# SCH_Force_Plate_Signal_Conditioning_Unit.net
KiCad netlist of a schematic drawn in EasyEDA
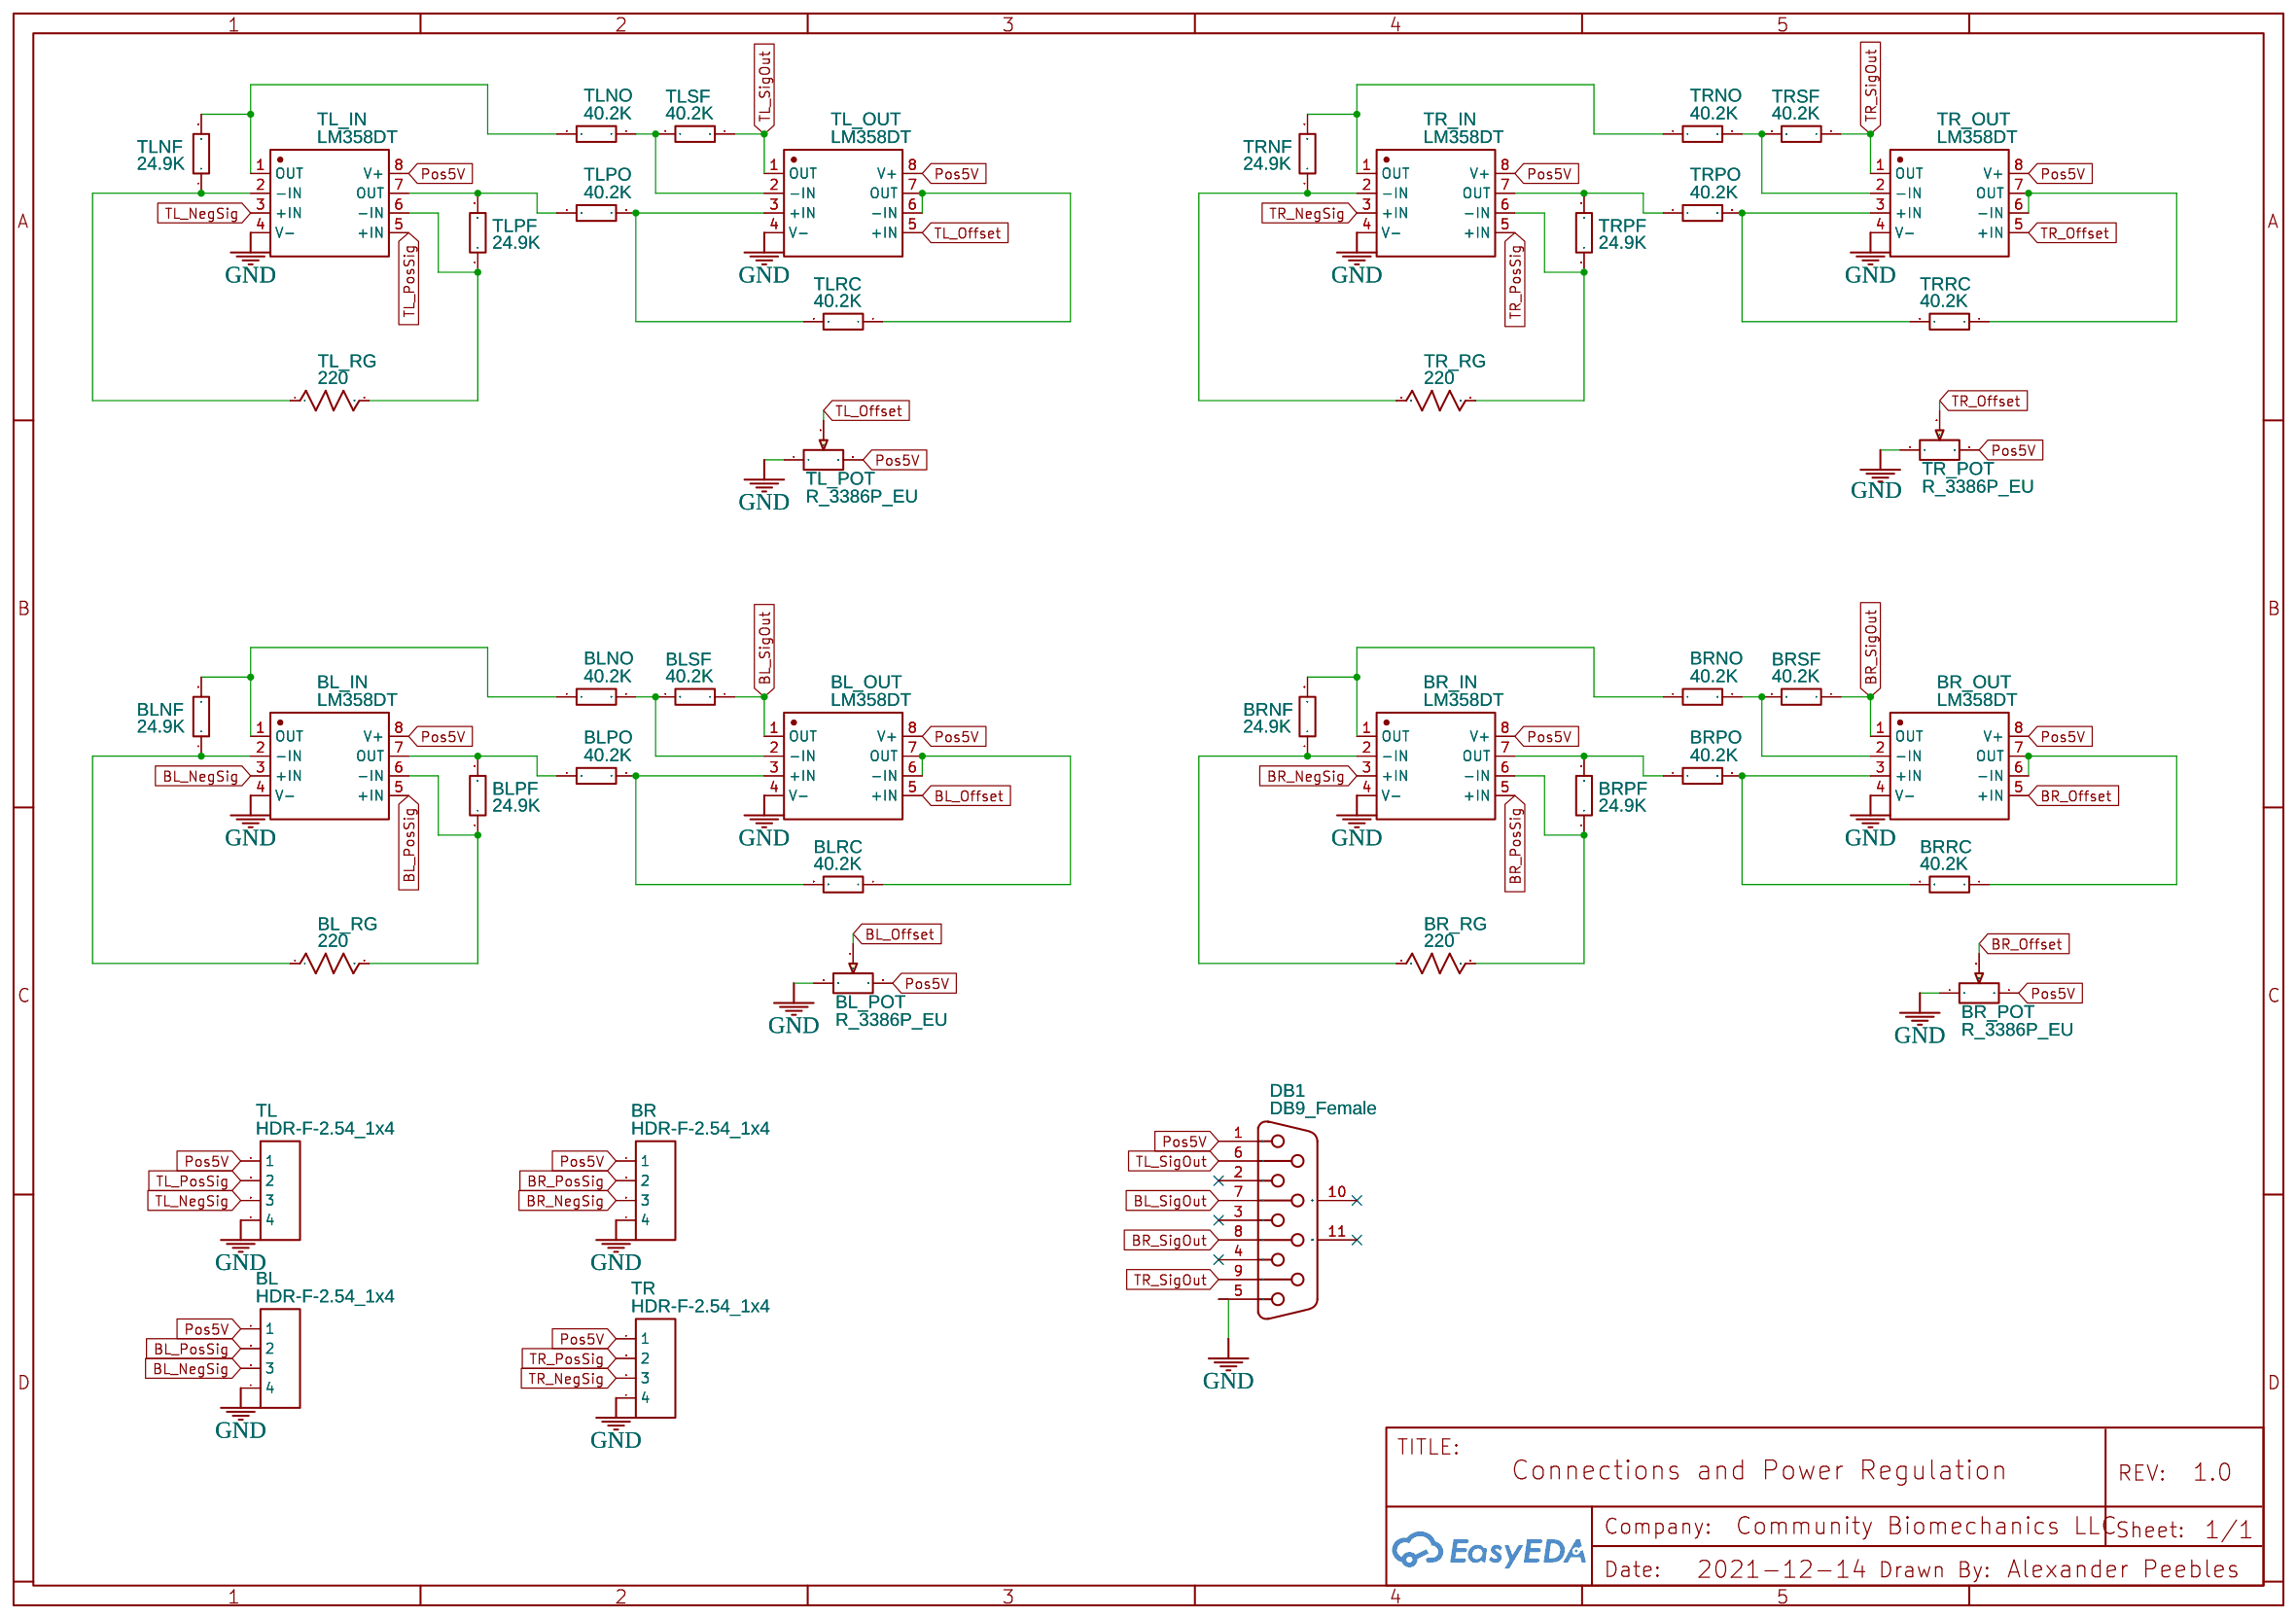
[diagram p0: schematic sheet]

(export (version "E")
  (design (tool "Eeschema 10.0.6"))
  (components
    (comp (ref "BL")
      (value "HDR-F-2.54_1x4")
      (fields (field (name "BOM_Supplier Part") "C225501"))
      (libsource (lib "") (part "HDR-F-2.54_1x4_1"))
    )
    (comp (ref "BLNF")
      (value "24.9K")
      (fields
        (field (name "BOM_Manufacturer Part") "0603WAF2492T5E")
        (field (name "BOM_Supplier Part") "C25962")
      )
      (libsource (lib "") (part "0603WAF2492T5E_7"))
    )
    (comp (ref "BLNO")
      (value "40.2K")
      (fields
        (field (name "BOM_Manufacturer Part") "0603WAF4022T5E")
        (field (name "BOM_Supplier Part") "C12447")
      )
      (libsource (lib "") (part "0603WAF4022T5E_8"))
    )
    (comp (ref "BLPF")
      (value "24.9K")
      (fields
        (field (name "BOM_Manufacturer Part") "0603WAF2492T5E")
        (field (name "BOM_Supplier Part") "C25962")
      )
      (libsource (lib "") (part "0603WAF2492T5E_2"))
    )
    (comp (ref "BLPO")
      (value "40.2K")
      (fields
        (field (name "BOM_Manufacturer Part") "0603WAF4022T5E")
        (field (name "BOM_Supplier Part") "C12447")
      )
      (libsource (lib "") (part "0603WAF4022T5E_11"))
    )
    (comp (ref "BLRC")
      (value "40.2K")
      (fields
        (field (name "BOM_Manufacturer Part") "0603WAF4022T5E")
        (field (name "BOM_Supplier Part") "C12447")
      )
      (libsource (lib "") (part "0603WAF4022T5E_1"))
    )
    (comp (ref "BLSF")
      (value "40.2K")
      (fields
        (field (name "BOM_Manufacturer Part") "0603WAF4022T5E")
        (field (name "BOM_Supplier Part") "C12447")
      )
      (libsource (lib "") (part "0603WAF4022T5E_15"))
    )
    (comp (ref "BL_IN")
      (value "LM358DT")
      (fields (field (name "BOM_Supplier Part") "C9418"))
      (libsource (lib "") (part "LM358DT_1"))
    )
    (comp (ref "BL_OUT")
      (value "LM358DT")
      (fields (field (name "BOM_Supplier Part") "C9418"))
      (libsource (lib "") (part "LM358DT_5"))
    )
    (comp (ref "BL_POT") (value "R_3386P_EU") (libsource (lib "") (part "R_3386P_EU_2")))
    (comp (ref "BL_RG") (value "220") (libsource (lib "") (part "R_AXIAL-0.4_US")))
    (comp (ref "BR")
      (value "HDR-F-2.54_1x4")
      (fields (field (name "BOM_Supplier Part") "C225501"))
      (libsource (lib "") (part "HDR-F-2.54_1x4"))
    )
    (comp (ref "BRNF")
      (value "24.9K")
      (fields
        (field (name "BOM_Manufacturer Part") "0603WAF2492T5E")
        (field (name "BOM_Supplier Part") "C25962")
      )
      (libsource (lib "") (part "0603WAF2492T5E_3"))
    )
    (comp (ref "BRNO")
      (value "40.2K")
      (fields
        (field (name "BOM_Manufacturer Part") "0603WAF4022T5E")
        (field (name "BOM_Supplier Part") "C12447")
      )
      (libsource (lib "") (part "0603WAF4022T5E_3"))
    )
    (comp (ref "BRPF")
      (value "24.9K")
      (fields
        (field (name "BOM_Manufacturer Part") "0603WAF2492T5E")
        (field (name "BOM_Supplier Part") "C25962")
      )
      (libsource (lib "") (part "0603WAF2492T5E_6"))
    )
    (comp (ref "BRPO")
      (value "40.2K")
      (fields
        (field (name "BOM_Manufacturer Part") "0603WAF4022T5E")
        (field (name "BOM_Supplier Part") "C12447")
      )
      (libsource (lib "") (part "0603WAF4022T5E_14"))
    )
    (comp (ref "BRRC")
      (value "40.2K")
      (fields
        (field (name "BOM_Manufacturer Part") "0603WAF4022T5E")
        (field (name "BOM_Supplier Part") "C12447")
      )
      (libsource (lib "") (part "0603WAF4022T5E_13"))
    )
    (comp (ref "BRSF")
      (value "40.2K")
      (fields
        (field (name "BOM_Manufacturer Part") "0603WAF4022T5E")
        (field (name "BOM_Supplier Part") "C12447")
      )
      (libsource (lib "") (part "0603WAF4022T5E_10"))
    )
    (comp (ref "BR_IN")
      (value "LM358DT")
      (fields (field (name "BOM_Supplier Part") "C9418"))
      (libsource (lib "") (part "LM358DT_2"))
    )
    (comp (ref "BR_OUT")
      (value "LM358DT")
      (fields (field (name "BOM_Supplier Part") "C9418"))
      (libsource (lib "") (part "LM358DT_3"))
    )
    (comp (ref "BR_POT") (value "R_3386P_EU") (libsource (lib "") (part "R_3386P_EU")))
    (comp (ref "BR_RG") (value "220") (libsource (lib "") (part "R_AXIAL-0.4_US_2")))
    (comp (ref "DB1")
      (value "DB9_Female")
      (fields (field (name "BOM_Supplier Part") "C141882"))
      (libsource (lib "") (part "DB9_Female"))
    )
    (comp (ref "TL")
      (value "HDR-F-2.54_1x4")
      (fields (field (name "BOM_Supplier Part") "C225501"))
      (libsource (lib "") (part "HDR-F-2.54_1x4_3"))
    )
    (comp (ref "TLNF")
      (value "24.9K")
      (fields
        (field (name "BOM_Manufacturer Part") "0603WAF2492T5E")
        (field (name "BOM_Supplier Part") "C25962")
      )
      (libsource (lib "") (part "0603WAF2492T5E_5"))
    )
    (comp (ref "TLNO")
      (value "40.2K")
      (fields
        (field (name "BOM_Manufacturer Part") "0603WAF4022T5E")
        (field (name "BOM_Supplier Part") "C12447")
      )
      (libsource (lib "") (part "0603WAF4022T5E_9"))
    )
    (comp (ref "TLPF")
      (value "24.9K")
      (fields
        (field (name "BOM_Manufacturer Part") "0603WAF2492T5E")
        (field (name "BOM_Supplier Part") "C25962")
      )
      (libsource (lib "") (part "0603WAF2492T5E"))
    )
    (comp (ref "TLPO")
      (value "40.2K")
      (fields
        (field (name "BOM_Manufacturer Part") "0603WAF4022T5E")
        (field (name "BOM_Supplier Part") "C12447")
      )
      (libsource (lib "") (part "0603WAF4022T5E_6"))
    )
    (comp (ref "TLRC")
      (value "40.2K")
      (fields
        (field (name "BOM_Manufacturer Part") "0603WAF4022T5E")
        (field (name "BOM_Supplier Part") "C12447")
      )
      (libsource (lib "") (part "0603WAF4022T5E_5"))
    )
    (comp (ref "TLSF")
      (value "40.2K")
      (fields
        (field (name "BOM_Manufacturer Part") "0603WAF4022T5E")
        (field (name "BOM_Supplier Part") "C12447")
      )
      (libsource (lib "") (part "0603WAF4022T5E_12"))
    )
    (comp (ref "TL_IN")
      (value "LM358DT")
      (fields (field (name "BOM_Supplier Part") "C9418"))
      (libsource (lib "") (part "LM358DT_6"))
    )
    (comp (ref "TL_OUT")
      (value "LM358DT")
      (fields (field (name "BOM_Supplier Part") "C9418"))
      (libsource (lib "") (part "LM358DT_4"))
    )
    (comp (ref "TL_POT") (value "R_3386P_EU") (libsource (lib "") (part "R_3386P_EU_3")))
    (comp (ref "TL_RG") (value "220") (libsource (lib "") (part "R_AXIAL-0.4_US_3")))
    (comp (ref "TR")
      (value "HDR-F-2.54_1x4")
      (fields (field (name "BOM_Supplier Part") "C225501"))
      (libsource (lib "") (part "HDR-F-2.54_1x4_2"))
    )
    (comp (ref "TRNF")
      (value "24.9K")
      (fields
        (field (name "BOM_Manufacturer Part") "0603WAF2492T5E")
        (field (name "BOM_Supplier Part") "C25962")
      )
      (libsource (lib "") (part "0603WAF2492T5E_4"))
    )
    (comp (ref "TRNO")
      (value "40.2K")
      (fields
        (field (name "BOM_Manufacturer Part") "0603WAF4022T5E")
        (field (name "BOM_Supplier Part") "C12447")
      )
      (libsource (lib "") (part "0603WAF4022T5E_2"))
    )
    (comp (ref "TRPF")
      (value "24.9K")
      (fields
        (field (name "BOM_Manufacturer Part") "0603WAF2492T5E")
        (field (name "BOM_Supplier Part") "C25962")
      )
      (libsource (lib "") (part "0603WAF2492T5E_1"))
    )
    (comp (ref "TRPO")
      (value "40.2K")
      (fields
        (field (name "BOM_Manufacturer Part") "0603WAF4022T5E")
        (field (name "BOM_Supplier Part") "C12447")
      )
      (libsource (lib "") (part "0603WAF4022T5E_4"))
    )
    (comp (ref "TRRC")
      (value "40.2K")
      (fields
        (field (name "BOM_Manufacturer Part") "0603WAF4022T5E")
        (field (name "BOM_Supplier Part") "C12447")
      )
      (libsource (lib "") (part "0603WAF4022T5E"))
    )
    (comp (ref "TRSF")
      (value "40.2K")
      (fields
        (field (name "BOM_Manufacturer Part") "0603WAF4022T5E")
        (field (name "BOM_Supplier Part") "C12447")
      )
      (libsource (lib "") (part "0603WAF4022T5E_7"))
    )
    (comp (ref "TR_IN")
      (value "LM358DT")
      (fields (field (name "BOM_Supplier Part") "C9418"))
      (libsource (lib "") (part "LM358DT"))
    )
    (comp (ref "TR_OUT")
      (value "LM358DT")
      (fields (field (name "BOM_Supplier Part") "C9418"))
      (libsource (lib "") (part "LM358DT_7"))
    )
    (comp (ref "TR_POT") (value "R_3386P_EU") (libsource (lib "") (part "R_3386P_EU_1")))
    (comp (ref "TR_RG") (value "220") (libsource (lib "") (part "R_AXIAL-0.4_US_1")))
  )
  (nets
    (net (code "1") (name "BL_NegSig") (class "Default")
      (node (ref "BL") (pin "3") (pinfunction "3_3") (pintype "unspecified"))
      (node (ref "BL_IN") (pin "3") (pinfunction "+IN_3") (pintype "unspecified"))
    )
    (net (code "2") (name "BL_Offset") (class "Default")
      (node (ref "BL_OUT") (pin "5") (pinfunction "+IN_5") (pintype "unspecified"))
      (node (ref "BL_POT") (pin "2") (pinfunction "2_2") (pintype "input"))
    )
    (net (code "3") (name "BL_PosSig") (class "Default")
      (node (ref "BL") (pin "2") (pinfunction "2_2") (pintype "unspecified"))
      (node (ref "BL_IN") (pin "5") (pinfunction "+IN_5") (pintype "unspecified"))
    )
    (net (code "4") (name "BL_SigOut") (class "Default")
      (node (ref "BLSF") (pin "1") (pinfunction "1_1") (pintype "input"))
      (node (ref "BL_OUT") (pin "1") (pinfunction "OUT_1") (pintype "unspecified"))
      (node (ref "DB1") (pin "7") (pinfunction "7_7") (pintype "input"))
    )
    (net (code "5") (name "BR_NegSig") (class "Default")
      (node (ref "BR") (pin "3") (pinfunction "3_3") (pintype "unspecified"))
      (node (ref "BR_IN") (pin "3") (pinfunction "+IN_3") (pintype "unspecified"))
    )
    (net (code "6") (name "BR_Offset") (class "Default")
      (node (ref "BR_OUT") (pin "5") (pinfunction "+IN_5") (pintype "unspecified"))
      (node (ref "BR_POT") (pin "2") (pinfunction "2_2") (pintype "input"))
    )
    (net (code "7") (name "BR_PosSig") (class "Default")
      (node (ref "BR") (pin "2") (pinfunction "2_2") (pintype "unspecified"))
      (node (ref "BR_IN") (pin "5") (pinfunction "+IN_5") (pintype "unspecified"))
    )
    (net (code "8") (name "BR_SigOut") (class "Default")
      (node (ref "BRSF") (pin "1") (pinfunction "1_1") (pintype "input"))
      (node (ref "BR_OUT") (pin "1") (pinfunction "OUT_1") (pintype "unspecified"))
      (node (ref "DB1") (pin "8") (pinfunction "8_8") (pintype "input"))
    )
    (net (code "9") (name "GND") (class "Default")
      (node (ref "BL") (pin "4") (pinfunction "4_4") (pintype "unspecified"))
      (node (ref "BL_IN") (pin "4") (pinfunction "V-_4") (pintype "unspecified"))
      (node (ref "BL_OUT") (pin "4") (pinfunction "V-_4") (pintype "unspecified"))
      (node (ref "BL_POT") (pin "1") (pinfunction "1_1") (pintype "input"))
      (node (ref "BR") (pin "4") (pinfunction "4_4") (pintype "unspecified"))
      (node (ref "BR_IN") (pin "4") (pinfunction "V-_4") (pintype "unspecified"))
      (node (ref "BR_OUT") (pin "4") (pinfunction "V-_4") (pintype "unspecified"))
      (node (ref "BR_POT") (pin "1") (pinfunction "1_1") (pintype "input"))
      (node (ref "DB1") (pin "5") (pinfunction "5_5") (pintype "input"))
      (node (ref "TL") (pin "4") (pinfunction "4_4") (pintype "unspecified"))
      (node (ref "TL_IN") (pin "4") (pinfunction "V-_4") (pintype "unspecified"))
      (node (ref "TL_OUT") (pin "4") (pinfunction "V-_4") (pintype "unspecified"))
      (node (ref "TL_POT") (pin "1") (pinfunction "1_1") (pintype "input"))
      (node (ref "TR") (pin "4") (pinfunction "4_4") (pintype "unspecified"))
      (node (ref "TR_IN") (pin "4") (pinfunction "V-_4") (pintype "unspecified"))
      (node (ref "TR_OUT") (pin "4") (pinfunction "V-_4") (pintype "unspecified"))
      (node (ref "TR_POT") (pin "1") (pinfunction "1_1") (pintype "input"))
    )
    (net (code "10") (name "Net-(BLNF-Pad1)") (class "Default")
      (node (ref "BLNF") (pin "1") (pinfunction "1_1") (pintype "input"))
      (node (ref "BL_IN") (pin "2") (pinfunction "-IN_2") (pintype "unspecified"))
      (node (ref "BL_RG") (pin "1") (pinfunction "1_1") (pintype "unspecified"))
    )
    (net (code "11") (name "Net-(BLNF-Pad2)") (class "Default")
      (node (ref "BLNF") (pin "2") (pinfunction "2_2") (pintype "input"))
      (node (ref "BLNO") (pin "1") (pinfunction "1_1") (pintype "input"))
      (node (ref "BL_IN") (pin "1") (pinfunction "OUT_1") (pintype "unspecified"))
    )
    (net (code "12") (name "Net-(BLNO-Pad2)") (class "Default")
      (node (ref "BLNO") (pin "2") (pinfunction "2_2") (pintype "input"))
      (node (ref "BLSF") (pin "2") (pinfunction "2_2") (pintype "input"))
      (node (ref "BL_OUT") (pin "2") (pinfunction "-IN_2") (pintype "unspecified"))
    )
    (net (code "13") (name "Net-(BLPF-Pad1)") (class "Default")
      (node (ref "BLPF") (pin "1") (pinfunction "1_1") (pintype "input"))
      (node (ref "BL_IN") (pin "6") (pinfunction "-IN_6") (pintype "unspecified"))
      (node (ref "BL_RG") (pin "2") (pinfunction "2_2") (pintype "unspecified"))
    )
    (net (code "14") (name "Net-(BLPF-Pad2)") (class "Default")
      (node (ref "BLPF") (pin "2") (pinfunction "2_2") (pintype "input"))
      (node (ref "BLPO") (pin "1") (pinfunction "1_1") (pintype "input"))
      (node (ref "BL_IN") (pin "7") (pinfunction "OUT_7") (pintype "unspecified"))
    )
    (net (code "15") (name "Net-(BLPO-Pad2)") (class "Default")
      (node (ref "BLPO") (pin "2") (pinfunction "2_2") (pintype "input"))
      (node (ref "BLRC") (pin "2") (pinfunction "2_2") (pintype "input"))
      (node (ref "BL_OUT") (pin "3") (pinfunction "+IN_3") (pintype "unspecified"))
    )
    (net (code "16") (name "Net-(BLRC-Pad1)") (class "Default")
      (node (ref "BLRC") (pin "1") (pinfunction "1_1") (pintype "input"))
      (node (ref "BL_OUT") (pin "6") (pinfunction "-IN_6") (pintype "unspecified"))
      (node (ref "BL_OUT") (pin "7") (pinfunction "OUT_7") (pintype "unspecified"))
    )
    (net (code "17") (name "Net-(BRNF-Pad1)") (class "Default")
      (node (ref "BRNF") (pin "1") (pinfunction "1_1") (pintype "input"))
      (node (ref "BR_IN") (pin "2") (pinfunction "-IN_2") (pintype "unspecified"))
      (node (ref "BR_RG") (pin "1") (pinfunction "1_1") (pintype "unspecified"))
    )
    (net (code "18") (name "Net-(BRNF-Pad2)") (class "Default")
      (node (ref "BRNF") (pin "2") (pinfunction "2_2") (pintype "input"))
      (node (ref "BRNO") (pin "1") (pinfunction "1_1") (pintype "input"))
      (node (ref "BR_IN") (pin "1") (pinfunction "OUT_1") (pintype "unspecified"))
    )
    (net (code "19") (name "Net-(BRNO-Pad2)") (class "Default")
      (node (ref "BRNO") (pin "2") (pinfunction "2_2") (pintype "input"))
      (node (ref "BRSF") (pin "2") (pinfunction "2_2") (pintype "input"))
      (node (ref "BR_OUT") (pin "2") (pinfunction "-IN_2") (pintype "unspecified"))
    )
    (net (code "20") (name "Net-(BRPF-Pad1)") (class "Default")
      (node (ref "BRPF") (pin "1") (pinfunction "1_1") (pintype "input"))
      (node (ref "BR_IN") (pin "6") (pinfunction "-IN_6") (pintype "unspecified"))
      (node (ref "BR_RG") (pin "2") (pinfunction "2_2") (pintype "unspecified"))
    )
    (net (code "21") (name "Net-(BRPF-Pad2)") (class "Default")
      (node (ref "BRPF") (pin "2") (pinfunction "2_2") (pintype "input"))
      (node (ref "BRPO") (pin "1") (pinfunction "1_1") (pintype "input"))
      (node (ref "BR_IN") (pin "7") (pinfunction "OUT_7") (pintype "unspecified"))
    )
    (net (code "22") (name "Net-(BRPO-Pad2)") (class "Default")
      (node (ref "BRPO") (pin "2") (pinfunction "2_2") (pintype "input"))
      (node (ref "BRRC") (pin "2") (pinfunction "2_2") (pintype "input"))
      (node (ref "BR_OUT") (pin "3") (pinfunction "+IN_3") (pintype "unspecified"))
    )
    (net (code "23") (name "Net-(BRRC-Pad1)") (class "Default")
      (node (ref "BRRC") (pin "1") (pinfunction "1_1") (pintype "input"))
      (node (ref "BR_OUT") (pin "6") (pinfunction "-IN_6") (pintype "unspecified"))
      (node (ref "BR_OUT") (pin "7") (pinfunction "OUT_7") (pintype "unspecified"))
    )
    (net (code "24") (name "Net-(TLNF-Pad1)") (class "Default")
      (node (ref "TLNF") (pin "1") (pinfunction "1_1") (pintype "input"))
      (node (ref "TL_IN") (pin "2") (pinfunction "-IN_2") (pintype "unspecified"))
      (node (ref "TL_RG") (pin "1") (pinfunction "1_1") (pintype "unspecified"))
    )
    (net (code "25") (name "Net-(TLNF-Pad2)") (class "Default")
      (node (ref "TLNF") (pin "2") (pinfunction "2_2") (pintype "input"))
      (node (ref "TLNO") (pin "1") (pinfunction "1_1") (pintype "input"))
      (node (ref "TL_IN") (pin "1") (pinfunction "OUT_1") (pintype "unspecified"))
    )
    (net (code "26") (name "Net-(TLNO-Pad2)") (class "Default")
      (node (ref "TLNO") (pin "2") (pinfunction "2_2") (pintype "input"))
      (node (ref "TLSF") (pin "2") (pinfunction "2_2") (pintype "input"))
      (node (ref "TL_OUT") (pin "2") (pinfunction "-IN_2") (pintype "unspecified"))
    )
    (net (code "27") (name "Net-(TLPF-Pad1)") (class "Default")
      (node (ref "TLPF") (pin "1") (pinfunction "1_1") (pintype "input"))
      (node (ref "TL_IN") (pin "6") (pinfunction "-IN_6") (pintype "unspecified"))
      (node (ref "TL_RG") (pin "2") (pinfunction "2_2") (pintype "unspecified"))
    )
    (net (code "28") (name "Net-(TLPF-Pad2)") (class "Default")
      (node (ref "TLPF") (pin "2") (pinfunction "2_2") (pintype "input"))
      (node (ref "TLPO") (pin "1") (pinfunction "1_1") (pintype "input"))
      (node (ref "TL_IN") (pin "7") (pinfunction "OUT_7") (pintype "unspecified"))
    )
    (net (code "29") (name "Net-(TLPO-Pad2)") (class "Default")
      (node (ref "TLPO") (pin "2") (pinfunction "2_2") (pintype "input"))
      (node (ref "TLRC") (pin "2") (pinfunction "2_2") (pintype "input"))
      (node (ref "TL_OUT") (pin "3") (pinfunction "+IN_3") (pintype "unspecified"))
    )
    (net (code "30") (name "Net-(TLRC-Pad1)") (class "Default")
      (node (ref "TLRC") (pin "1") (pinfunction "1_1") (pintype "input"))
      (node (ref "TL_OUT") (pin "6") (pinfunction "-IN_6") (pintype "unspecified"))
      (node (ref "TL_OUT") (pin "7") (pinfunction "OUT_7") (pintype "unspecified"))
    )
    (net (code "31") (name "Net-(TRNF-Pad1)") (class "Default")
      (node (ref "TRNF") (pin "1") (pinfunction "1_1") (pintype "input"))
      (node (ref "TR_IN") (pin "2") (pinfunction "-IN_2") (pintype "unspecified"))
      (node (ref "TR_RG") (pin "1") (pinfunction "1_1") (pintype "unspecified"))
    )
    (net (code "32") (name "Net-(TRNF-Pad2)") (class "Default")
      (node (ref "TRNF") (pin "2") (pinfunction "2_2") (pintype "input"))
      (node (ref "TRNO") (pin "1") (pinfunction "1_1") (pintype "input"))
      (node (ref "TR_IN") (pin "1") (pinfunction "OUT_1") (pintype "unspecified"))
    )
    (net (code "33") (name "Net-(TRNO-Pad2)") (class "Default")
      (node (ref "TRNO") (pin "2") (pinfunction "2_2") (pintype "input"))
      (node (ref "TRSF") (pin "2") (pinfunction "2_2") (pintype "input"))
      (node (ref "TR_OUT") (pin "2") (pinfunction "-IN_2") (pintype "unspecified"))
    )
    (net (code "34") (name "Net-(TRPF-Pad1)") (class "Default")
      (node (ref "TRPF") (pin "1") (pinfunction "1_1") (pintype "input"))
      (node (ref "TR_IN") (pin "6") (pinfunction "-IN_6") (pintype "unspecified"))
      (node (ref "TR_RG") (pin "2") (pinfunction "2_2") (pintype "unspecified"))
    )
    (net (code "35") (name "Net-(TRPF-Pad2)") (class "Default")
      (node (ref "TRPF") (pin "2") (pinfunction "2_2") (pintype "input"))
      (node (ref "TRPO") (pin "1") (pinfunction "1_1") (pintype "input"))
      (node (ref "TR_IN") (pin "7") (pinfunction "OUT_7") (pintype "unspecified"))
    )
    (net (code "36") (name "Net-(TRPO-Pad2)") (class "Default")
      (node (ref "TRPO") (pin "2") (pinfunction "2_2") (pintype "input"))
      (node (ref "TRRC") (pin "2") (pinfunction "2_2") (pintype "input"))
      (node (ref "TR_OUT") (pin "3") (pinfunction "+IN_3") (pintype "unspecified"))
    )
    (net (code "37") (name "Net-(TRRC-Pad1)") (class "Default")
      (node (ref "TRRC") (pin "1") (pinfunction "1_1") (pintype "input"))
      (node (ref "TR_OUT") (pin "6") (pinfunction "-IN_6") (pintype "unspecified"))
      (node (ref "TR_OUT") (pin "7") (pinfunction "OUT_7") (pintype "unspecified"))
    )
    (net (code "38") (name "Pos5V") (class "Default")
      (node (ref "BL") (pin "1") (pinfunction "1_1") (pintype "unspecified"))
      (node (ref "BL_IN") (pin "8") (pinfunction "V+_8") (pintype "unspecified"))
      (node (ref "BL_OUT") (pin "8") (pinfunction "V+_8") (pintype "unspecified"))
      (node (ref "BL_POT") (pin "3") (pinfunction "3_3") (pintype "input"))
      (node (ref "BR") (pin "1") (pinfunction "1_1") (pintype "unspecified"))
      (node (ref "BR_IN") (pin "8") (pinfunction "V+_8") (pintype "unspecified"))
      (node (ref "BR_OUT") (pin "8") (pinfunction "V+_8") (pintype "unspecified"))
      (node (ref "BR_POT") (pin "3") (pinfunction "3_3") (pintype "input"))
      (node (ref "DB1") (pin "1") (pinfunction "1_1") (pintype "input"))
      (node (ref "TL") (pin "1") (pinfunction "1_1") (pintype "unspecified"))
      (node (ref "TL_IN") (pin "8") (pinfunction "V+_8") (pintype "unspecified"))
      (node (ref "TL_OUT") (pin "8") (pinfunction "V+_8") (pintype "unspecified"))
      (node (ref "TL_POT") (pin "3") (pinfunction "3_3") (pintype "input"))
      (node (ref "TR") (pin "1") (pinfunction "1_1") (pintype "unspecified"))
      (node (ref "TR_IN") (pin "8") (pinfunction "V+_8") (pintype "unspecified"))
      (node (ref "TR_OUT") (pin "8") (pinfunction "V+_8") (pintype "unspecified"))
      (node (ref "TR_POT") (pin "3") (pinfunction "3_3") (pintype "input"))
    )
    (net (code "39") (name "TL_NegSig") (class "Default")
      (node (ref "TL") (pin "3") (pinfunction "3_3") (pintype "unspecified"))
      (node (ref "TL_IN") (pin "3") (pinfunction "+IN_3") (pintype "unspecified"))
    )
    (net (code "40") (name "TL_Offset") (class "Default")
      (node (ref "TL_OUT") (pin "5") (pinfunction "+IN_5") (pintype "unspecified"))
      (node (ref "TL_POT") (pin "2") (pinfunction "2_2") (pintype "input"))
    )
    (net (code "41") (name "TL_PosSig") (class "Default")
      (node (ref "TL") (pin "2") (pinfunction "2_2") (pintype "unspecified"))
      (node (ref "TL_IN") (pin "5") (pinfunction "+IN_5") (pintype "unspecified"))
    )
    (net (code "42") (name "TL_SigOut") (class "Default")
      (node (ref "DB1") (pin "6") (pinfunction "6_6") (pintype "input"))
      (node (ref "TLSF") (pin "1") (pinfunction "1_1") (pintype "input"))
      (node (ref "TL_OUT") (pin "1") (pinfunction "OUT_1") (pintype "unspecified"))
    )
    (net (code "43") (name "TR_NegSig") (class "Default")
      (node (ref "TR") (pin "3") (pinfunction "3_3") (pintype "unspecified"))
      (node (ref "TR_IN") (pin "3") (pinfunction "+IN_3") (pintype "unspecified"))
    )
    (net (code "44") (name "TR_Offset") (class "Default")
      (node (ref "TR_OUT") (pin "5") (pinfunction "+IN_5") (pintype "unspecified"))
      (node (ref "TR_POT") (pin "2") (pinfunction "2_2") (pintype "input"))
    )
    (net (code "45") (name "TR_PosSig") (class "Default")
      (node (ref "TR") (pin "2") (pinfunction "2_2") (pintype "unspecified"))
      (node (ref "TR_IN") (pin "5") (pinfunction "+IN_5") (pintype "unspecified"))
    )
    (net (code "46") (name "TR_SigOut") (class "Default")
      (node (ref "DB1") (pin "9") (pinfunction "9_9") (pintype "input"))
      (node (ref "TRSF") (pin "1") (pinfunction "1_1") (pintype "input"))
      (node (ref "TR_OUT") (pin "1") (pinfunction "OUT_1") (pintype "unspecified"))
    )
    (net (code "47") (name "unconnected-(DB1-MH1-Pad10)") (class "Default")
      (node (ref "DB1") (pin "10") (pinfunction "MH1_10") (pintype "input+no_connect"))
    )
    (net (code "48") (name "unconnected-(DB1-MH2-Pad11)") (class "Default")
      (node (ref "DB1") (pin "11") (pinfunction "MH2_11") (pintype "input+no_connect"))
    )
    (net (code "49") (name "unconnected-(DB1-Pad2)") (class "Default")
      (node (ref "DB1") (pin "2") (pinfunction "2_2") (pintype "input+no_connect"))
    )
    (net (code "50") (name "unconnected-(DB1-Pad3)") (class "Default")
      (node (ref "DB1") (pin "3") (pinfunction "3_3") (pintype "input+no_connect"))
    )
    (net (code "51") (name "unconnected-(DB1-Pad4)") (class "Default")
      (node (ref "DB1") (pin "4") (pinfunction "4_4") (pintype "input+no_connect"))
    )
  )
)
